# config-bank6.net
KiCad netlist of a schematic drawn in Altium Designer
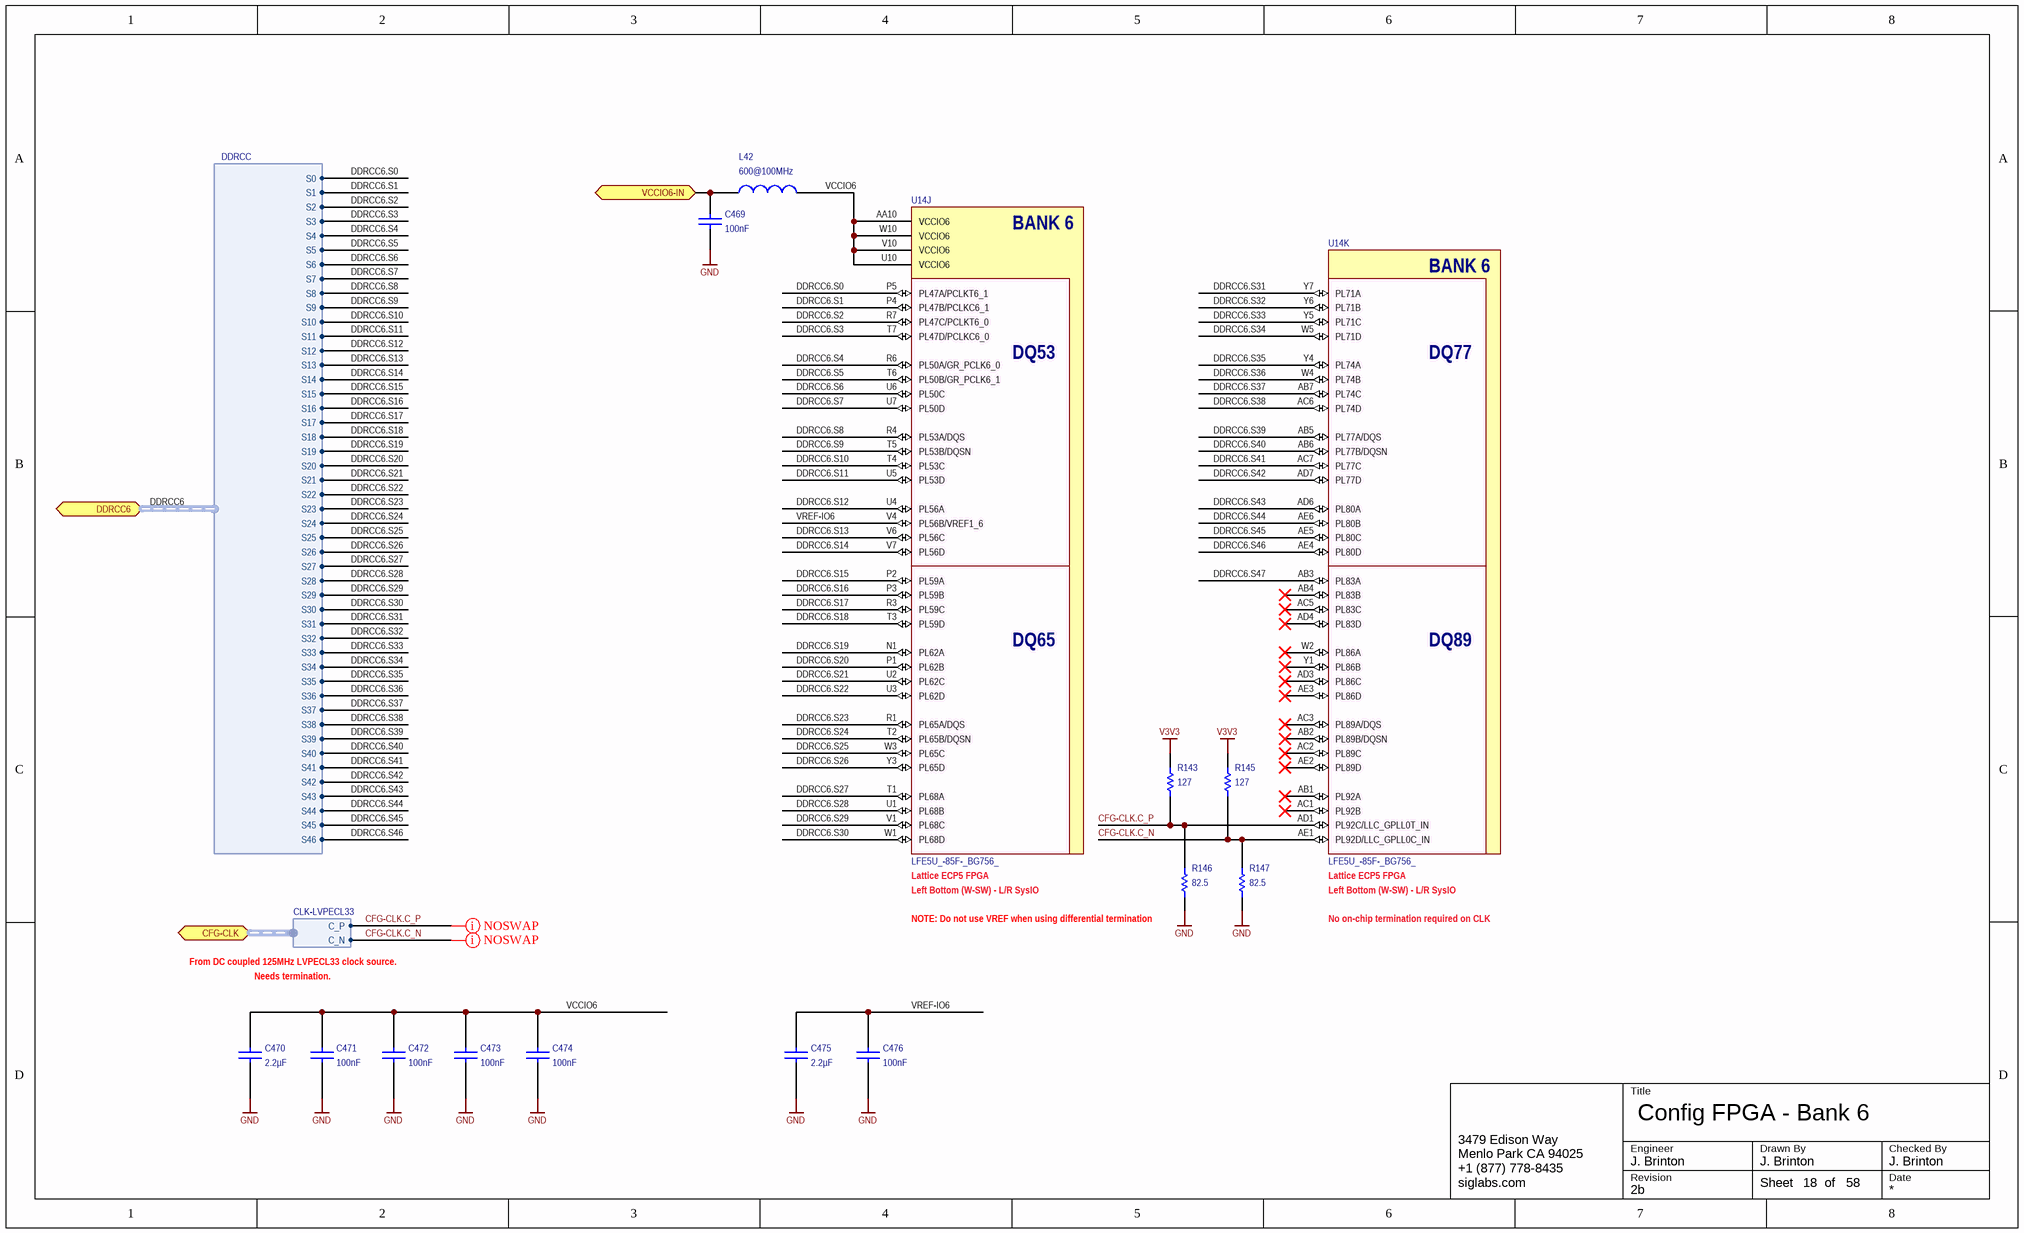
[diagram p0: config-bank6.SchDoc]

(export (version "E")
  (design (tool "Eeschema 10.0.6"))
  (components
    (comp (ref "C469")
      (value "100nF")
      (footprint "generic:CAPC1005X56N")
      (description "Ceramic Capacitor 100nF ±10% 16V X7R 0402")
      (fields (field (name "MANUFACTURER") "Murata") (field (name "TOLERANCE") "±10%"))
      (libsource (lib "murata") (part "GRM155R71A104KA01J"))
    )
    (comp (ref "C470")
      (value "2.2µF")
      (footprint "generic:CAPC1608X90N")
      (description "Ceramic Capacitor 2.2uF ±10% 10V X7R 0603")
      (fields (field (name "MANUFACTURER") "Murata") (field (name "TOLERANCE") "±10%"))
      (libsource (lib "murata") (part "GRM188R71A225KE15D"))
    )
    (comp (ref "C471")
      (value "100nF")
      (footprint "generic:CAPC1005X56N")
      (description "Ceramic Capacitor 100nF ±10% 16V X7R 0402")
      (fields (field (name "MANUFACTURER") "Murata") (field (name "TOLERANCE") "±10%"))
      (libsource (lib "murata") (part "GRM155R71A104KA01J"))
    )
    (comp (ref "C472")
      (value "100nF")
      (footprint "generic:CAPC1005X56N")
      (description "Ceramic Capacitor 100nF ±10% 16V X7R 0402")
      (fields (field (name "MANUFACTURER") "Murata") (field (name "TOLERANCE") "±10%"))
      (libsource (lib "murata") (part "GRM155R71A104KA01J"))
    )
    (comp (ref "C473")
      (value "100nF")
      (footprint "generic:CAPC1005X56N")
      (description "Ceramic Capacitor 100nF ±10% 16V X7R 0402")
      (fields (field (name "MANUFACTURER") "Murata") (field (name "TOLERANCE") "±10%"))
      (libsource (lib "murata") (part "GRM155R71A104KA01J"))
    )
    (comp (ref "C474")
      (value "100nF")
      (footprint "generic:CAPC1005X56N")
      (description "Ceramic Capacitor 100nF ±10% 16V X7R 0402")
      (fields (field (name "MANUFACTURER") "Murata") (field (name "TOLERANCE") "±10%"))
      (libsource (lib "murata") (part "GRM155R71A104KA01J"))
    )
    (comp (ref "C475")
      (value "2.2µF")
      (footprint "generic:CAPC1608X90N")
      (description "Ceramic Capacitor 2.2uF ±10% 10V X7R 0603")
      (fields (field (name "MANUFACTURER") "Murata") (field (name "TOLERANCE") "±10%"))
      (libsource (lib "murata") (part "GRM188R71A225KE15D"))
    )
    (comp (ref "C476")
      (value "100nF")
      (footprint "generic:CAPC1005X56N")
      (description "Ceramic Capacitor 100nF ±10% 16V X7R 0402")
      (fields (field (name "MANUFACTURER") "Murata") (field (name "TOLERANCE") "±10%"))
      (libsource (lib "murata") (part "GRM155R71A104KA01J"))
    )
    (comp (ref "L42")
      (value "600@100MHz")
      (footprint "0402")
      (description "Ferrite Bead 600-Ohm @ 100MHz 900mA 0402")
      (fields (field (name "MANUFACTURER") "Murata") (field (name "TOLERANCE") "±25%"))
      (libsource (lib "Graviton") (part "IND 0402"))
    )
    (comp (ref "R143")
      (value "127")
      (footprint "generic:0402")
      (description "Thin Film Resistor 127 ±0.1% 0402")
      (fields (field (name "MANUFACTURER") "Panasonic") (field (name "TOLERANCE") "±0.1%"))
      (libsource (lib "Graviton") (part "RES 0402"))
    )
    (comp (ref "R145")
      (value "127")
      (footprint "generic:0402")
      (description "Thin Film Resistor 127 ±0.1% 0402")
      (fields (field (name "MANUFACTURER") "Panasonic") (field (name "TOLERANCE") "±0.1%"))
      (libsource (lib "Graviton") (part "RES 0402"))
    )
    (comp (ref "R146")
      (value "82.5")
      (footprint "generic:0402")
      (description "Thin Film Resistor 82.5 ±0.1% 0402")
      (fields (field (name "MANUFACTURER") "Panasonic") (field (name "TOLERANCE") "±0.1%"))
      (libsource (lib "Graviton") (part "RES 0402"))
    )
    (comp (ref "R147")
      (value "82.5")
      (footprint "generic:0402")
      (description "Thin Film Resistor 82.5 ±0.1% 0402")
      (fields (field (name "MANUFACTURER") "Panasonic") (field (name "TOLERANCE") "±0.1%"))
      (libsource (lib "Graviton") (part "RES 0402"))
    )
    (comp (ref "U14")
      (value "LFE5U_-85F-_BG756_")
      (footprint "lattice:caBGA756")
      (description "ECP5 FPGA, 85k LUT, 756-caBGA")
      (fields (field (name "MANUFACTURER") "Lattice Semiconductor"))
      (libsource (lib "lattice") (part "LFE5U_-85F-_BG756_"))
    )
  )
  (nets
    (net (code "3") (name "/CFG-CLK.C_N") (class "Default")
      (node (ref "R145") (pin "1") (pinfunction "1_1") (pintype "passive"))
      (node (ref "R147") (pin "2") (pinfunction "2_2") (pintype "passive"))
      (node (ref "U14") (pin "AE1") (pinfunction "PL92D/LLC_GPLL0C_IN_AE1") (pintype "bidirectional"))
    )
    (net (code "4") (name "/CFG-CLK.C_P") (class "Default")
      (node (ref "R143") (pin "1") (pinfunction "1_1") (pintype "passive"))
      (node (ref "R146") (pin "2") (pinfunction "2_2") (pintype "passive"))
      (node (ref "U14") (pin "AD1") (pinfunction "PL92C/LLC_GPLL0T_IN_AD1") (pintype "bidirectional"))
    )
    (net (code "5") (name "/DDRCC6.S0") (class "Default")
      (node (ref "U14") (pin "P5") (pinfunction "PL47A/PCLKT6_1_P5") (pintype "bidirectional"))
    )
    (net (code "6") (name "/DDRCC6.S1") (class "Default")
      (node (ref "U14") (pin "P4") (pinfunction "PL47B/PCLKC6_1_P4") (pintype "bidirectional"))
    )
    (net (code "7") (name "/DDRCC6.S2") (class "Default")
      (node (ref "U14") (pin "R7") (pinfunction "PL47C/PCLKT6_0_R7") (pintype "bidirectional"))
    )
    (net (code "8") (name "/DDRCC6.S3") (class "Default")
      (node (ref "U14") (pin "T7") (pinfunction "PL47D/PCLKC6_0_T7") (pintype "bidirectional"))
    )
    (net (code "9") (name "/DDRCC6.S4") (class "Default")
      (node (ref "U14") (pin "R6") (pinfunction "PL50A/GR_PCLK6_0_R6") (pintype "bidirectional"))
    )
    (net (code "10") (name "/DDRCC6.S5") (class "Default")
      (node (ref "U14") (pin "T6") (pinfunction "PL50B/GR_PCLK6_1_T6") (pintype "bidirectional"))
    )
    (net (code "11") (name "/DDRCC6.S6") (class "Default")
      (node (ref "U14") (pin "U6") (pinfunction "PL50C_U6") (pintype "bidirectional"))
    )
    (net (code "12") (name "/DDRCC6.S7") (class "Default")
      (node (ref "U14") (pin "U7") (pinfunction "PL50D_U7") (pintype "bidirectional"))
    )
    (net (code "13") (name "/DDRCC6.S8") (class "Default")
      (node (ref "U14") (pin "R4") (pinfunction "PL53A/DQS_R4") (pintype "bidirectional"))
    )
    (net (code "14") (name "/DDRCC6.S9") (class "Default")
      (node (ref "U14") (pin "T5") (pinfunction "PL53B/DQSN_T5") (pintype "bidirectional"))
    )
    (net (code "15") (name "/DDRCC6.S10") (class "Default")
      (node (ref "U14") (pin "T4") (pinfunction "PL53C_T4") (pintype "bidirectional"))
    )
    (net (code "16") (name "/DDRCC6.S11") (class "Default")
      (node (ref "U14") (pin "U5") (pinfunction "PL53D_U5") (pintype "bidirectional"))
    )
    (net (code "17") (name "/DDRCC6.S12") (class "Default")
      (node (ref "U14") (pin "U4") (pinfunction "PL56A_U4") (pintype "bidirectional"))
    )
    (net (code "18") (name "/DDRCC6.S13") (class "Default")
      (node (ref "U14") (pin "V6") (pinfunction "PL56C_V6") (pintype "bidirectional"))
    )
    (net (code "19") (name "/DDRCC6.S14") (class "Default")
      (node (ref "U14") (pin "V7") (pinfunction "PL56D_V7") (pintype "bidirectional"))
    )
    (net (code "20") (name "/DDRCC6.S15") (class "Default")
      (node (ref "U14") (pin "P2") (pinfunction "PL59A_P2") (pintype "bidirectional"))
    )
    (net (code "21") (name "/DDRCC6.S16") (class "Default")
      (node (ref "U14") (pin "P3") (pinfunction "PL59B_P3") (pintype "bidirectional"))
    )
    (net (code "22") (name "/DDRCC6.S17") (class "Default")
      (node (ref "U14") (pin "R3") (pinfunction "PL59C_R3") (pintype "bidirectional"))
    )
    (net (code "23") (name "/DDRCC6.S18") (class "Default")
      (node (ref "U14") (pin "T3") (pinfunction "PL59D_T3") (pintype "bidirectional"))
    )
    (net (code "24") (name "/DDRCC6.S19") (class "Default")
      (node (ref "U14") (pin "N1") (pinfunction "PL62A_N1") (pintype "bidirectional"))
    )
    (net (code "25") (name "/DDRCC6.S20") (class "Default")
      (node (ref "U14") (pin "P1") (pinfunction "PL62B_P1") (pintype "bidirectional"))
    )
    (net (code "26") (name "/DDRCC6.S21") (class "Default")
      (node (ref "U14") (pin "U2") (pinfunction "PL62C_U2") (pintype "bidirectional"))
    )
    (net (code "27") (name "/DDRCC6.S22") (class "Default")
      (node (ref "U14") (pin "U3") (pinfunction "PL62D_U3") (pintype "bidirectional"))
    )
    (net (code "28") (name "/DDRCC6.S23") (class "Default")
      (node (ref "U14") (pin "R1") (pinfunction "PL65A/DQS_R1") (pintype "bidirectional"))
    )
    (net (code "29") (name "/DDRCC6.S24") (class "Default")
      (node (ref "U14") (pin "T2") (pinfunction "PL65B/DQSN_T2") (pintype "bidirectional"))
    )
    (net (code "30") (name "/DDRCC6.S25") (class "Default")
      (node (ref "U14") (pin "W3") (pinfunction "PL65C_W3") (pintype "bidirectional"))
    )
    (net (code "31") (name "/DDRCC6.S26") (class "Default")
      (node (ref "U14") (pin "Y3") (pinfunction "PL65D_Y3") (pintype "bidirectional"))
    )
    (net (code "32") (name "/DDRCC6.S27") (class "Default")
      (node (ref "U14") (pin "T1") (pinfunction "PL68A_T1") (pintype "bidirectional"))
    )
    (net (code "33") (name "/DDRCC6.S28") (class "Default")
      (node (ref "U14") (pin "U1") (pinfunction "PL68B_U1") (pintype "bidirectional"))
    )
    (net (code "34") (name "/DDRCC6.S29") (class "Default")
      (node (ref "U14") (pin "V1") (pinfunction "PL68C_V1") (pintype "bidirectional"))
    )
    (net (code "35") (name "/DDRCC6.S30") (class "Default")
      (node (ref "U14") (pin "W1") (pinfunction "PL68D_W1") (pintype "bidirectional"))
    )
    (net (code "36") (name "/DDRCC6.S31") (class "Default")
      (node (ref "U14") (pin "Y7") (pinfunction "PL71A_Y7") (pintype "bidirectional"))
    )
    (net (code "37") (name "/DDRCC6.S32") (class "Default")
      (node (ref "U14") (pin "Y6") (pinfunction "PL71B_Y6") (pintype "bidirectional"))
    )
    (net (code "38") (name "/DDRCC6.S33") (class "Default")
      (node (ref "U14") (pin "Y5") (pinfunction "PL71C_Y5") (pintype "bidirectional"))
    )
    (net (code "39") (name "/DDRCC6.S34") (class "Default")
      (node (ref "U14") (pin "W5") (pinfunction "PL71D_W5") (pintype "bidirectional"))
    )
    (net (code "40") (name "/DDRCC6.S35") (class "Default")
      (node (ref "U14") (pin "Y4") (pinfunction "PL74A_Y4") (pintype "bidirectional"))
    )
    (net (code "41") (name "/DDRCC6.S36") (class "Default")
      (node (ref "U14") (pin "W4") (pinfunction "PL74B_W4") (pintype "bidirectional"))
    )
    (net (code "42") (name "/DDRCC6.S37") (class "Default")
      (node (ref "U14") (pin "AB7") (pinfunction "PL74C_AB7") (pintype "bidirectional"))
    )
    (net (code "43") (name "/DDRCC6.S38") (class "Default")
      (node (ref "U14") (pin "AC6") (pinfunction "PL74D_AC6") (pintype "bidirectional"))
    )
    (net (code "44") (name "/DDRCC6.S39") (class "Default")
      (node (ref "U14") (pin "AB5") (pinfunction "PL77A/DQS_AB5") (pintype "bidirectional"))
    )
    (net (code "45") (name "/DDRCC6.S40") (class "Default")
      (node (ref "U14") (pin "AB6") (pinfunction "PL77B/DQSN_AB6") (pintype "bidirectional"))
    )
    (net (code "46") (name "/DDRCC6.S41") (class "Default")
      (node (ref "U14") (pin "AC7") (pinfunction "PL77C_AC7") (pintype "bidirectional"))
    )
    (net (code "47") (name "/DDRCC6.S42") (class "Default")
      (node (ref "U14") (pin "AD7") (pinfunction "PL77D_AD7") (pintype "bidirectional"))
    )
    (net (code "48") (name "/DDRCC6.S43") (class "Default")
      (node (ref "U14") (pin "AD6") (pinfunction "PL80A_AD6") (pintype "bidirectional"))
    )
    (net (code "49") (name "/DDRCC6.S44") (class "Default")
      (node (ref "U14") (pin "AE6") (pinfunction "PL80B_AE6") (pintype "bidirectional"))
    )
    (net (code "50") (name "/DDRCC6.S45") (class "Default")
      (node (ref "U14") (pin "AE5") (pinfunction "PL80C_AE5") (pintype "bidirectional"))
    )
    (net (code "51") (name "/DDRCC6.S46") (class "Default")
      (node (ref "U14") (pin "AE4") (pinfunction "PL80D_AE4") (pintype "bidirectional"))
    )
    (net (code "52") (name "/DDRCC6.S47") (class "Default")
      (node (ref "U14") (pin "AB3") (pinfunction "PL83A_AB3") (pintype "bidirectional"))
    )
    (net (code "54") (name "/VCCIO6") (class "Default")
      (node (ref "C470") (pin "2") (pinfunction "2_2") (pintype "passive"))
      (node (ref "C471") (pin "2") (pinfunction "2_2") (pintype "passive"))
      (node (ref "C472") (pin "2") (pinfunction "2_2") (pintype "passive"))
      (node (ref "C473") (pin "2") (pinfunction "2_2") (pintype "passive"))
      (node (ref "C474") (pin "2") (pinfunction "2_2") (pintype "passive"))
      (node (ref "L42") (pin "1") (pinfunction "1_1") (pintype "passive"))
      (node (ref "U14") (pin "AA10") (pinfunction "VCCIO6_AA10") (pintype "power_in"))
      (node (ref "U14") (pin "U10") (pinfunction "VCCIO6_U10") (pintype "power_in"))
      (node (ref "U14") (pin "V10") (pinfunction "VCCIO6_V10") (pintype "power_in"))
      (node (ref "U14") (pin "W10") (pinfunction "VCCIO6_W10") (pintype "power_in"))
    )
    (net (code "55") (name "/VCCIO6-IN") (class "Default")
      (node (ref "C469") (pin "2") (pinfunction "2_2") (pintype "passive"))
      (node (ref "L42") (pin "2") (pinfunction "2_2") (pintype "passive"))
    )
    (net (code "56") (name "/VREF-IO6") (class "Default")
      (node (ref "C475") (pin "2") (pinfunction "2_2") (pintype "passive"))
      (node (ref "C476") (pin "2") (pinfunction "2_2") (pintype "passive"))
      (node (ref "U14") (pin "V4") (pinfunction "PL56B/VREF1_6_V4") (pintype "bidirectional"))
    )
    (net (code "58") (name "GND") (class "Default")
      (node (ref "C469") (pin "1") (pinfunction "1_1") (pintype "passive"))
      (node (ref "C470") (pin "1") (pinfunction "1_1") (pintype "passive"))
      (node (ref "C471") (pin "1") (pinfunction "1_1") (pintype "passive"))
      (node (ref "C472") (pin "1") (pinfunction "1_1") (pintype "passive"))
      (node (ref "C473") (pin "1") (pinfunction "1_1") (pintype "passive"))
      (node (ref "C474") (pin "1") (pinfunction "1_1") (pintype "passive"))
      (node (ref "C475") (pin "1") (pinfunction "1_1") (pintype "passive"))
      (node (ref "C476") (pin "1") (pinfunction "1_1") (pintype "passive"))
      (node (ref "R146") (pin "1") (pinfunction "1_1") (pintype "passive"))
      (node (ref "R147") (pin "1") (pinfunction "1_1") (pintype "passive"))
    )
    (net (code "59") (name "V3V3") (class "Default")
      (node (ref "R143") (pin "2") (pinfunction "2_2") (pintype "passive"))
      (node (ref "R145") (pin "2") (pinfunction "2_2") (pintype "passive"))
    )
    (net (code "60") (name "unconnected-(U14K-PL83B-PadAB4)") (class "Default")
      (node (ref "U14") (pin "AB4") (pinfunction "PL83B_AB4") (pintype "bidirectional+no_connect"))
    )
    (net (code "61") (name "unconnected-(U14K-PL83C-PadAC5)") (class "Default")
      (node (ref "U14") (pin "AC5") (pinfunction "PL83C_AC5") (pintype "bidirectional+no_connect"))
    )
    (net (code "62") (name "unconnected-(U14K-PL83D-PadAD4)") (class "Default")
      (node (ref "U14") (pin "AD4") (pinfunction "PL83D_AD4") (pintype "bidirectional+no_connect"))
    )
    (net (code "63") (name "unconnected-(U14K-PL86A-PadW2)") (class "Default")
      (node (ref "U14") (pin "W2") (pinfunction "PL86A_W2") (pintype "bidirectional+no_connect"))
    )
    (net (code "64") (name "unconnected-(U14K-PL86B-PadY1)") (class "Default")
      (node (ref "U14") (pin "Y1") (pinfunction "PL86B_Y1") (pintype "bidirectional+no_connect"))
    )
    (net (code "65") (name "unconnected-(U14K-PL86C-PadAD3)") (class "Default")
      (node (ref "U14") (pin "AD3") (pinfunction "PL86C_AD3") (pintype "bidirectional+no_connect"))
    )
    (net (code "66") (name "unconnected-(U14K-PL86D-PadAE3)") (class "Default")
      (node (ref "U14") (pin "AE3") (pinfunction "PL86D_AE3") (pintype "bidirectional+no_connect"))
    )
    (net (code "67") (name "unconnected-(U14K-PL89A{slash}DQS-PadAC3)") (class "Default")
      (node (ref "U14") (pin "AC3") (pinfunction "PL89A/DQS_AC3") (pintype "bidirectional+no_connect"))
    )
    (net (code "68") (name "unconnected-(U14K-PL89B{slash}DQSN-PadAB2)") (class "Default")
      (node (ref "U14") (pin "AB2") (pinfunction "PL89B/DQSN_AB2") (pintype "bidirectional+no_connect"))
    )
    (net (code "69") (name "unconnected-(U14K-PL89C-PadAC2)") (class "Default")
      (node (ref "U14") (pin "AC2") (pinfunction "PL89C_AC2") (pintype "bidirectional+no_connect"))
    )
    (net (code "70") (name "unconnected-(U14K-PL89D-PadAE2)") (class "Default")
      (node (ref "U14") (pin "AE2") (pinfunction "PL89D_AE2") (pintype "bidirectional+no_connect"))
    )
    (net (code "71") (name "unconnected-(U14K-PL92A-PadAB1)") (class "Default")
      (node (ref "U14") (pin "AB1") (pinfunction "PL92A_AB1") (pintype "bidirectional+no_connect"))
    )
    (net (code "72") (name "unconnected-(U14K-PL92B-PadAC1)") (class "Default")
      (node (ref "U14") (pin "AC1") (pinfunction "PL92B_AC1") (pintype "bidirectional+no_connect"))
    )
  )
)
